# SwitchEthernet_-_Rev_A5.net
KiCad netlist of a schematic drawn in EAGLE
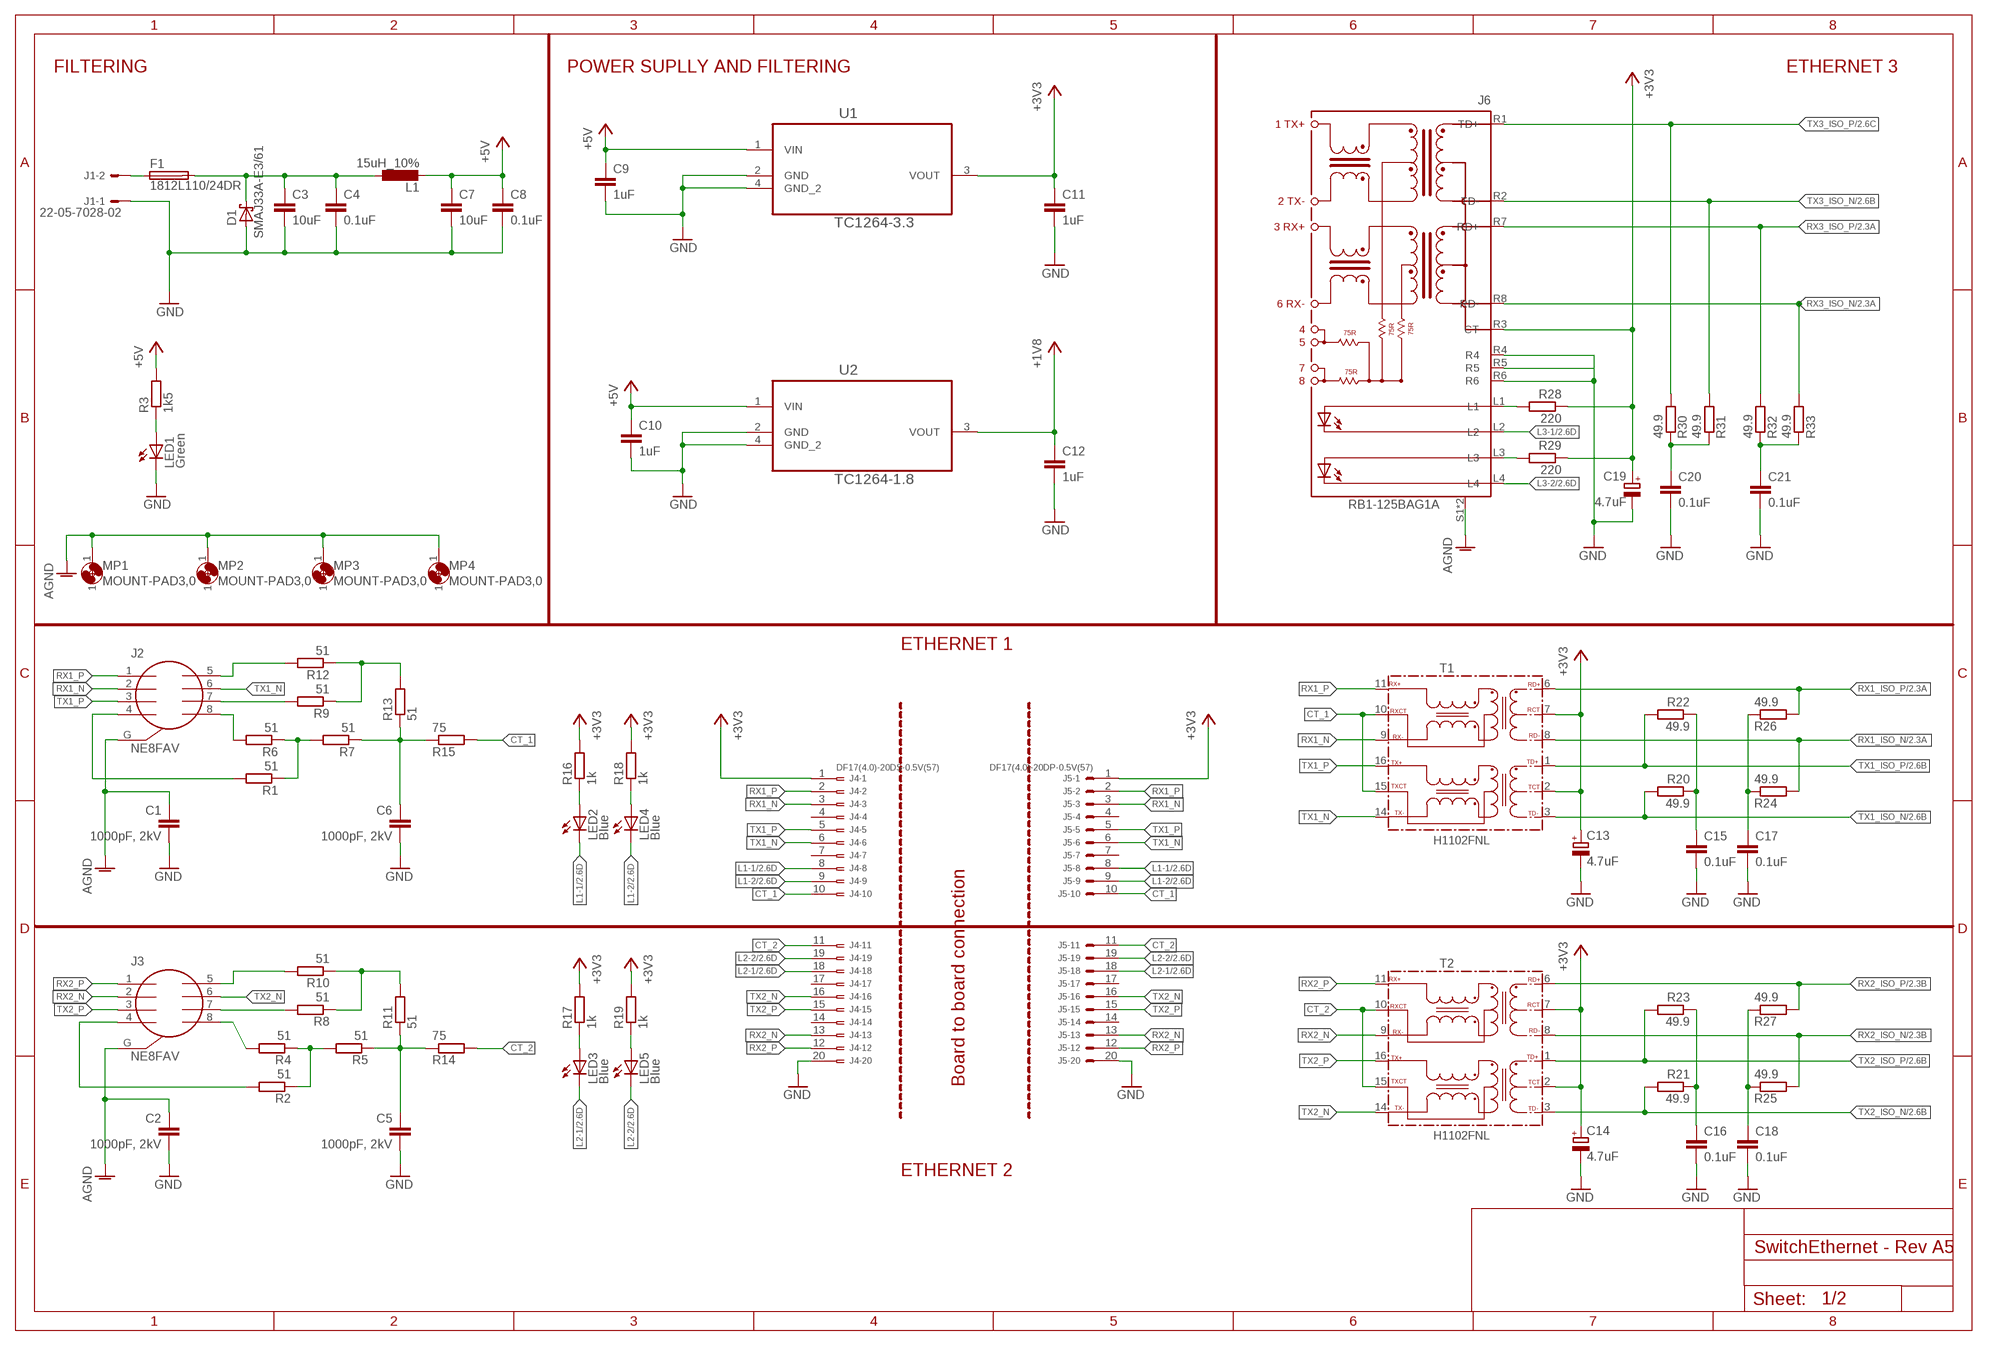
[diagram p0: schematic, sheet 1]
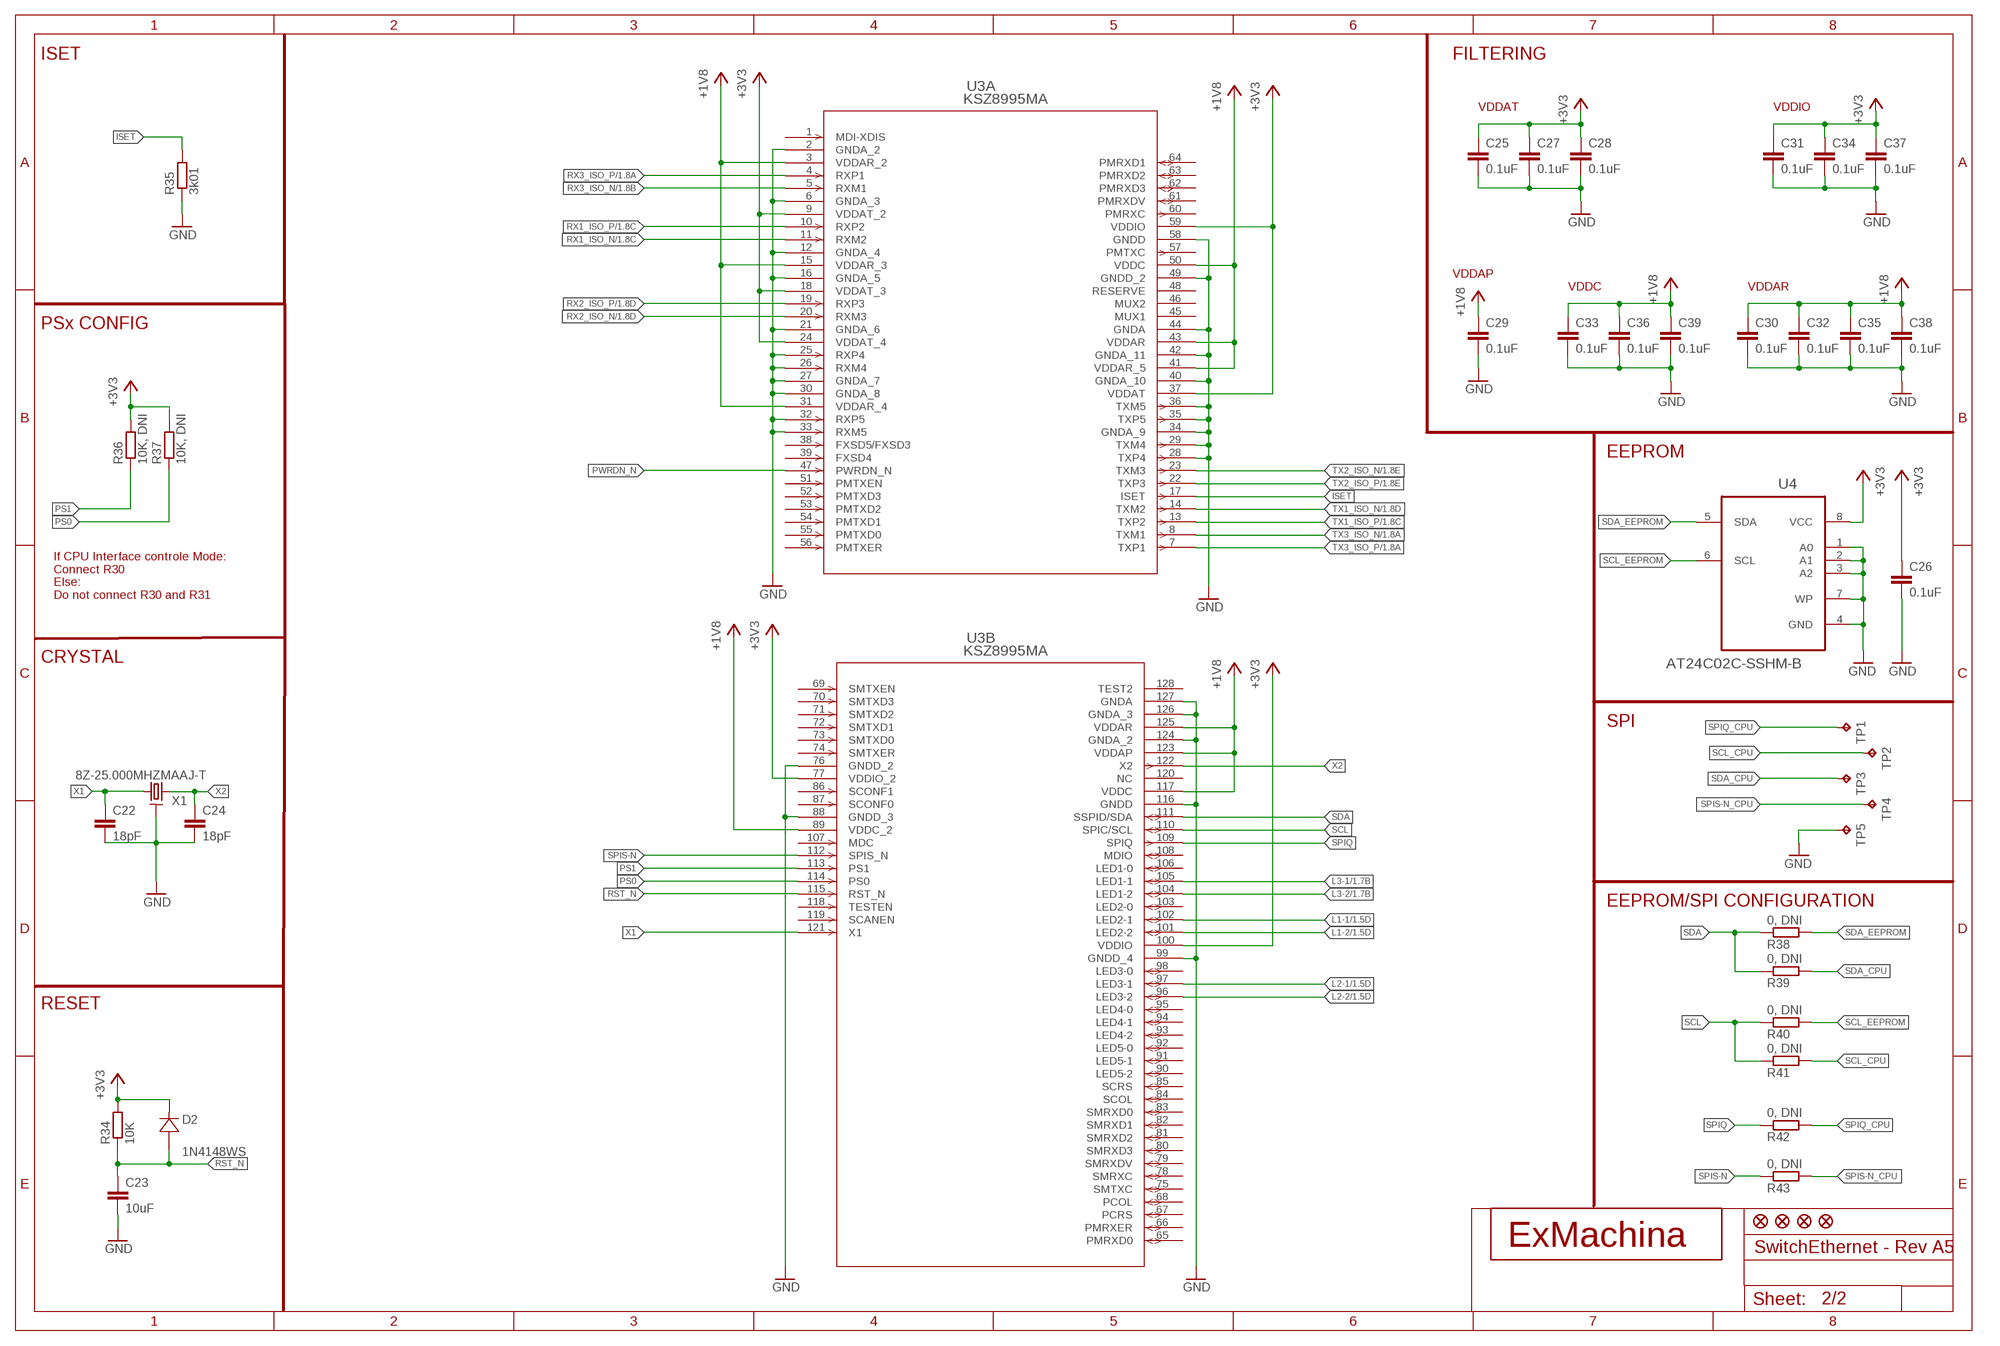
[diagram p1: schematic, sheet 2]

(export (version "E")
  (design (tool "Eeschema 10.0.6"))
  (components
    (comp (ref "C22")
      (value "18pF")
      (footprint "eagle-import:C0603")
      (fields (field (name "MPN") "MC0603N180J500CT"))
      (libsource (lib "eagle-import") (part "C-EUC0603"))
    )
    (comp (ref "C23")
      (value "10uF")
      (footprint "eagle-import:C0603")
      (fields (field (name "MPN") "GRM188R60J106ME47D"))
      (libsource (lib "eagle-import") (part "C-EUC0603"))
    )
    (comp (ref "C24")
      (value "18pF")
      (footprint "eagle-import:C0603")
      (fields (field (name "MPN") "MC0603N180J500CT"))
      (libsource (lib "eagle-import") (part "C-EUC0603"))
    )
    (comp (ref "C25")
      (value "0.1uF")
      (footprint "eagle-import:C0603")
      (fields (field (name "MPN") "MC0603B104K160CT"))
      (libsource (lib "eagle-import") (part "C-EUC0603"))
    )
    (comp (ref "C26")
      (value "0.1uF")
      (footprint "eagle-import:C0603")
      (fields (field (name "MPN") "MC0603B104K160CT"))
      (libsource (lib "eagle-import") (part "C-EUC0603"))
    )
    (comp (ref "C27")
      (value "0.1uF")
      (footprint "eagle-import:C0603")
      (fields (field (name "MPN") "MC0603B104K160CT"))
      (libsource (lib "eagle-import") (part "C-EUC0603"))
    )
    (comp (ref "C28")
      (value "0.1uF")
      (footprint "eagle-import:C0603")
      (fields (field (name "MPN") "MC0603B104K160CT"))
      (libsource (lib "eagle-import") (part "C-EUC0603"))
    )
    (comp (ref "C29")
      (value "0.1uF")
      (footprint "eagle-import:C0603")
      (fields (field (name "MPN") "MC0603B104K160CT"))
      (libsource (lib "eagle-import") (part "C-EUC0603"))
    )
    (comp (ref "C30")
      (value "0.1uF")
      (footprint "eagle-import:C0603")
      (fields (field (name "MPN") "MC0603B104K160CT"))
      (libsource (lib "eagle-import") (part "C-EUC0603"))
    )
    (comp (ref "C31")
      (value "0.1uF")
      (footprint "eagle-import:C0603")
      (fields (field (name "MPN") "MC0603B104K160CT"))
      (libsource (lib "eagle-import") (part "C-EUC0603"))
    )
    (comp (ref "C32")
      (value "0.1uF")
      (footprint "eagle-import:C0603")
      (fields (field (name "MPN") "MC0603B104K160CT"))
      (libsource (lib "eagle-import") (part "C-EUC0603"))
    )
    (comp (ref "C33")
      (value "0.1uF")
      (footprint "eagle-import:C0603")
      (fields (field (name "MPN") "MC0603B104K160CT"))
      (libsource (lib "eagle-import") (part "C-EUC0603"))
    )
    (comp (ref "C34")
      (value "0.1uF")
      (footprint "eagle-import:C0603")
      (fields (field (name "MPN") "MC0603B104K160CT"))
      (libsource (lib "eagle-import") (part "C-EUC0603"))
    )
    (comp (ref "C35")
      (value "0.1uF")
      (footprint "eagle-import:C0603")
      (fields (field (name "MPN") "MC0603B104K160CT"))
      (libsource (lib "eagle-import") (part "C-EUC0603"))
    )
    (comp (ref "C36")
      (value "0.1uF")
      (footprint "eagle-import:C0603")
      (fields (field (name "MPN") "MC0603B104K160CT"))
      (libsource (lib "eagle-import") (part "C-EUC0603"))
    )
    (comp (ref "C37")
      (value "0.1uF")
      (footprint "eagle-import:C0603")
      (fields (field (name "MPN") "MC0603B104K160CT"))
      (libsource (lib "eagle-import") (part "C-EUC0603"))
    )
    (comp (ref "C38")
      (value "0.1uF")
      (footprint "eagle-import:C0603")
      (fields (field (name "MPN") "MC0603B104K160CT"))
      (libsource (lib "eagle-import") (part "C-EUC0603"))
    )
    (comp (ref "C39")
      (value "0.1uF")
      (footprint "eagle-import:C0603")
      (fields (field (name "MPN") "MC0603B104K160CT"))
      (libsource (lib "eagle-import") (part "C-EUC0603"))
    )
    (comp (ref "D2")
      (value "1N4148WS")
      (footprint "eagle-import:SOD323-W")
      (fields (field (name "MPN") "1N4148WS."))
      (libsource (lib "eagle-import") (part "1N4148WS"))
    )
    (comp (ref "JP1")
      (value "FIDUCIAL1X2")
      (footprint "eagle-import:FIDUCIAL-1X2")
      (libsource (lib "eagle-import") (part "FIDUCIAL1X2"))
    )
    (comp (ref "JP2")
      (value "FIDUCIAL1X2")
      (footprint "eagle-import:FIDUCIAL-1X2")
      (libsource (lib "eagle-import") (part "FIDUCIAL1X2"))
    )
    (comp (ref "JP3")
      (value "FIDUCIAL1X2")
      (footprint "eagle-import:FIDUCIAL-1X2")
      (libsource (lib "eagle-import") (part "FIDUCIAL1X2"))
    )
    (comp (ref "JP4")
      (value "FIDUCIAL1X2")
      (footprint "eagle-import:FIDUCIAL-1X2")
      (libsource (lib "eagle-import") (part "FIDUCIAL1X2"))
    )
    (comp (ref "R34")
      (value "10K")
      (footprint "eagle-import:R0603")
      (fields (field (name "MF") "Multicomp Passives") (field (name "MPN") "MC0063W0603110K"))
      (libsource (lib "eagle-import") (part "R-EU_R0603"))
    )
    (comp (ref "R35")
      (value "3k01")
      (footprint "eagle-import:R0603")
      (fields (field (name "MPN") "MC0063W060313K01"))
      (libsource (lib "eagle-import") (part "R-EU_R0603"))
    )
    (comp (ref "R36")
      (value "10K, DNI")
      (footprint "eagle-import:R0603")
      (fields (field (name "MF") "Multicomp Passives") (field (name "MPN") "MC0063W0603110K"))
      (libsource (lib "eagle-import") (part "R-EU_R0603"))
    )
    (comp (ref "R37")
      (value "10K, DNI")
      (footprint "eagle-import:R0603")
      (fields (field (name "MF") "Multicomp Passives") (field (name "MPN") "MC0063W0603110K"))
      (libsource (lib "eagle-import") (part "R-EU_R0603"))
    )
    (comp (ref "R38")
      (value "0, DNI")
      (footprint "eagle-import:R0603")
      (fields (field (name "MF") "Multicomp Passives") (field (name "MPN") "MC0603WG00000T5E-TC"))
      (libsource (lib "eagle-import") (part "R-EU_R0603"))
    )
    (comp (ref "R39")
      (value "0, DNI")
      (footprint "eagle-import:R0603")
      (fields (field (name "MF") "Multicomp Passives") (field (name "MPN") "MC0603WG00000T5E-TC"))
      (libsource (lib "eagle-import") (part "R-EU_R0603"))
    )
    (comp (ref "R40")
      (value "0, DNI")
      (footprint "eagle-import:R0603")
      (fields (field (name "MF") "Multicomp Passives") (field (name "MPN") "MC0603WG00000T5E-TC"))
      (libsource (lib "eagle-import") (part "R-EU_R0603"))
    )
    (comp (ref "R41")
      (value "0, DNI")
      (footprint "eagle-import:R0603")
      (fields (field (name "MF") "Multicomp Passives") (field (name "MPN") "MC0603WG00000T5E-TC"))
      (libsource (lib "eagle-import") (part "R-EU_R0603"))
    )
    (comp (ref "R42")
      (value "0, DNI")
      (footprint "eagle-import:R0603")
      (fields (field (name "MF") "Multicomp Passives") (field (name "MPN") "MC0603WG00000T5E-TC"))
      (libsource (lib "eagle-import") (part "R-EU_R0603"))
    )
    (comp (ref "R43")
      (value "0, DNI")
      (footprint "eagle-import:R0603")
      (fields (field (name "MF") "Multicomp Passives") (field (name "MPN") "MC0603WG00000T5E-TC"))
      (libsource (lib "eagle-import") (part "R-EU_R0603"))
    )
    (comp (ref "T3")
      (value "EXMACHINA-LOGO-NAME")
      (footprint "eagle-import:EXM-LOGO-BASELINE")
      (libsource (lib "eagle-import") (part "EXMACHINA-LOGO-NAME"))
    )
    (comp (ref "TP1")
      (value "TPB1,27")
      (footprint "eagle-import:B1,27")
      (libsource (lib "eagle-import") (part "TPB1,27"))
    )
    (comp (ref "TP2")
      (value "TPB1,27")
      (footprint "eagle-import:B1,27")
      (libsource (lib "eagle-import") (part "TPB1,27"))
    )
    (comp (ref "TP3")
      (value "TPB1,27")
      (footprint "eagle-import:B1,27")
      (libsource (lib "eagle-import") (part "TPB1,27"))
    )
    (comp (ref "TP4")
      (value "TPB1,27")
      (footprint "eagle-import:B1,27")
      (libsource (lib "eagle-import") (part "TPB1,27"))
    )
    (comp (ref "TP5")
      (value "TPB1,27")
      (footprint "eagle-import:B1,27")
      (libsource (lib "eagle-import") (part "TPB1,27"))
    )
    (comp (ref "U3")
      (value "KSZ8995MA")
      (footprint "eagle-import:PQFP-128_MQL")
      (fields
        (field (name "MANUFACTURER_PART_NUMBER") "ksz8995ma")
        (field (name "OC_FARNELL") "2509844")
        (field (name "OC_NEWARK") "unknown")
        (field (name "COPYRIGHT") "Copyright (C) 2015 Accelerated Designs. All rights reserved")
      )
      (libsource (lib "eagle-import") (part "KSZ8995MA"))
    )
    (comp (ref "U4")
      (value "AT24C02C-SSHM-B")
      (footprint "eagle-import:SOIC127P600X175-8N")
      (fields (field (name "OC_FARNELL") "1971995"))
      (libsource (lib "eagle-import") (part "AT24C02C-SSHM-B"))
    )
    (comp (ref "X1")
      (value "8Z-25.000MHZMAAJ-T")
      (footprint "eagle-import:SMD2.5X2")
      (fields (field (name "MPN") "8Z-25.000MAAJ-T"))
      (libsource (lib "eagle-import") (part "8Z-25.000MHZMAAJ-T"))
    )
    (comp (ref "C1")
      (value "1000pF, 2kV")
      (footprint "eagle-import:C1206")
      (fields (field (name "MPN") "MC1206B102K202CT"))
      (libsource (lib "eagle-import") (part "C-EUC1206"))
    )
    (comp (ref "C2")
      (value "1000pF, 2kV")
      (footprint "eagle-import:C1206")
      (fields (field (name "MPN") "MC1206B102K202CT"))
      (libsource (lib "eagle-import") (part "C-EUC1206"))
    )
    (comp (ref "C3")
      (value "10uF")
      (footprint "eagle-import:C0603")
      (fields (field (name "MPN") "GRM188R60J106ME47D"))
      (libsource (lib "eagle-import") (part "C-EUC0603"))
    )
    (comp (ref "C4")
      (value "0.1uF")
      (footprint "eagle-import:C0603")
      (fields (field (name "MPN") "MC0603B104K160CT"))
      (libsource (lib "eagle-import") (part "C-EUC0603"))
    )
    (comp (ref "C5")
      (value "1000pF, 2kV")
      (footprint "eagle-import:C1206")
      (fields (field (name "MPN") "MC1206B102K202CT"))
      (libsource (lib "eagle-import") (part "C-EUC1206"))
    )
    (comp (ref "C6")
      (value "1000pF, 2kV")
      (footprint "eagle-import:C1206")
      (fields (field (name "MPN") "MC1206B102K202CT"))
      (libsource (lib "eagle-import") (part "C-EUC1206"))
    )
    (comp (ref "C7")
      (value "10uF")
      (footprint "eagle-import:C0603")
      (fields (field (name "MPN") "GRM188R60J106ME47D"))
      (libsource (lib "eagle-import") (part "C-EUC0603"))
    )
    (comp (ref "C8")
      (value "0.1uF")
      (footprint "eagle-import:C0603")
      (fields (field (name "MPN") "MC0603B104K160CT"))
      (libsource (lib "eagle-import") (part "C-EUC0603"))
    )
    (comp (ref "C9")
      (value "1uF")
      (footprint "eagle-import:C0603")
      (fields (field (name "MPN") "MC0603B105K160CT"))
      (libsource (lib "eagle-import") (part "C-EUC0603"))
    )
    (comp (ref "C10")
      (value "1uF")
      (footprint "eagle-import:C0603")
      (fields (field (name "MPN") "MC0603B105K160CT"))
      (libsource (lib "eagle-import") (part "C-EUC0603"))
    )
    (comp (ref "C11")
      (value "1uF")
      (footprint "eagle-import:C0603")
      (fields (field (name "MPN") "MC0603B105K160CT"))
      (libsource (lib "eagle-import") (part "C-EUC0603"))
    )
    (comp (ref "C12")
      (value "1uF")
      (footprint "eagle-import:C0603")
      (fields (field (name "MPN") "MC0603B105K160CT"))
      (libsource (lib "eagle-import") (part "C-EUC0603"))
    )
    (comp (ref "C13")
      (value "4.7uF")
      (footprint "eagle-import:CT3216")
      (fields (field (name "MPN") "MCCTA475M010"))
      (libsource (lib "eagle-import") (part "CPOL-EUCT3216"))
    )
    (comp (ref "C14")
      (value "4.7uF")
      (footprint "eagle-import:CT3216")
      (fields (field (name "MPN") "MCCTA475M010"))
      (libsource (lib "eagle-import") (part "CPOL-EUCT3216"))
    )
    (comp (ref "C15")
      (value "0.1uF")
      (footprint "eagle-import:C0603")
      (fields (field (name "MPN") "MC0603B104K160CT"))
      (libsource (lib "eagle-import") (part "C-EUC0603"))
    )
    (comp (ref "C16")
      (value "0.1uF")
      (footprint "eagle-import:C0603")
      (fields (field (name "MPN") "MC0603B104K160CT"))
      (libsource (lib "eagle-import") (part "C-EUC0603"))
    )
    (comp (ref "C17")
      (value "0.1uF")
      (footprint "eagle-import:C0603")
      (fields (field (name "MPN") "MC0603B104K160CT"))
      (libsource (lib "eagle-import") (part "C-EUC0603"))
    )
    (comp (ref "C18")
      (value "0.1uF")
      (footprint "eagle-import:C0603")
      (fields (field (name "MPN") "MC0603B104K160CT"))
      (libsource (lib "eagle-import") (part "C-EUC0603"))
    )
    (comp (ref "C19")
      (value "4.7uF")
      (footprint "eagle-import:CT3216")
      (fields (field (name "MPN") "MCCTA475M010"))
      (libsource (lib "eagle-import") (part "CPOL-EUCT3216"))
    )
    (comp (ref "C20")
      (value "0.1uF")
      (footprint "eagle-import:C0603")
      (fields (field (name "MPN") "MC0603B104K160CT"))
      (libsource (lib "eagle-import") (part "C-EUC0603"))
    )
    (comp (ref "C21")
      (value "0.1uF")
      (footprint "eagle-import:C0603")
      (fields (field (name "MPN") "MC0603B104K160CT"))
      (libsource (lib "eagle-import") (part "C-EUC0603"))
    )
    (comp (ref "D1")
      (value "SMAJ33A-E3/61")
      (footprint "eagle-import:DIODE_DO-214AC")
      (fields
        (field (name "RSPARTNUMBER") "7103462")
        (field (name "COPYRIGHT") "Copyright (C) 2015 Accelerated Designs. All rights reserved")
      )
      (libsource (lib "eagle-import") (part "SMAJ33A-E3/61"))
    )
    (comp (ref "F1")
      (value "1812L110/24DR")
      (footprint "eagle-import:LITTLEFUSE_SMD")
      (libsource (lib "eagle-import") (part "1812L110/24DR"))
    )
    (comp (ref "J1")
      (value "22-05-7028-02")
      (footprint "eagle-import:7395-02")
      (fields (field (name "MPN") "22-05-7028") (field (name "OC_NEWARK") "25M1728"))
      (libsource (lib "eagle-import") (part "22-?-0205-7028"))
    )
    (comp (ref "J2")
      (value "NE8FAV")
      (footprint "eagle-import:NE8FAV")
      (fields (field (name "MF") "NEUTRIK") (field (name "OC_FARNELL") "1202031"))
      (libsource (lib "eagle-import") (part "NE8FAV"))
    )
    (comp (ref "J3")
      (value "NE8FAV")
      (footprint "eagle-import:NE8FAV")
      (fields (field (name "MF") "NEUTRIK") (field (name "OC_FARNELL") "1202031"))
      (libsource (lib "eagle-import") (part "NE8FAV"))
    )
    (comp (ref "J4")
      (value "DF17(4.0)-20DS-0.5V(57)")
      (footprint "eagle-import:DF17-20DS")
      (fields (field (name "MPN") "DF17(4.0)-20DS-0.5V(57)") (field (name "OC_NEWARK") "69W0567"))
      (libsource (lib "eagle-import") (part "DF17(?)-20DS-0.5V(57)4.0"))
    )
    (comp (ref "J5")
      (value "DF17(4.0)-20DP-0.5V(57)")
      (footprint "eagle-import:DF17-20DP")
      (fields (field (name "MPN") "DF17(4.0)-20DP-0.5V(57)") (field (name "OC_NEWARK") "69W0566"))
      (libsource (lib "eagle-import") (part "DF17(?)-20DP-0.5V(57)4.0"))
    )
    (comp (ref "J6")
      (value "RB1-125BAG1A")
      (footprint "eagle-import:WIZNET_RB1-125BAG1A")
      (libsource (lib "eagle-import") (part "RB1-125BAG1A"))
    )
    (comp (ref "L1")
      (value "15uH_10%")
      (footprint "eagle-import:L4532M")
      (fields (field (name "MPN") "LQH43CN150K03L"))
      (libsource (lib "eagle-import") (part "L-EUL4532C"))
    )
    (comp (ref "LED1")
      (value "Green")
      (footprint "eagle-import:CHIP-LED0603")
      (fields (field (name "MPN") "OVS-0604"))
      (libsource (lib "eagle-import") (part "LEDCHIP-LED0603"))
    )
    (comp (ref "LED2")
      (value "Blue")
      (footprint "eagle-import:CHIP-LED0603")
      (fields (field (name "MPN") "OVS-0603"))
      (libsource (lib "eagle-import") (part "LEDCHIP-LED0603"))
    )
    (comp (ref "LED3")
      (value "Blue")
      (footprint "eagle-import:CHIP-LED0603")
      (fields (field (name "MPN") "OVS-0603"))
      (libsource (lib "eagle-import") (part "LEDCHIP-LED0603"))
    )
    (comp (ref "LED4")
      (value "Blue")
      (footprint "eagle-import:CHIP-LED0603")
      (fields (field (name "MPN") "OVS-0603"))
      (libsource (lib "eagle-import") (part "LEDCHIP-LED0603"))
    )
    (comp (ref "LED5")
      (value "Blue")
      (footprint "eagle-import:CHIP-LED0603")
      (fields (field (name "MPN") "OVS-0603"))
      (libsource (lib "eagle-import") (part "LEDCHIP-LED0603"))
    )
    (comp (ref "MP1")
      (value "MOUNT-PAD3,0")
      (footprint "eagle-import:P3,0")
      (libsource (lib "eagle-import") (part "MOUNT-PAD3,0"))
    )
    (comp (ref "MP2")
      (value "MOUNT-PAD3,0")
      (footprint "eagle-import:P3,0")
      (libsource (lib "eagle-import") (part "MOUNT-PAD3,0"))
    )
    (comp (ref "MP3")
      (value "MOUNT-PAD3,0")
      (footprint "eagle-import:P3,0")
      (libsource (lib "eagle-import") (part "MOUNT-PAD3,0"))
    )
    (comp (ref "MP4")
      (value "MOUNT-PAD3,0")
      (footprint "eagle-import:P3,0")
      (libsource (lib "eagle-import") (part "MOUNT-PAD3,0"))
    )
    (comp (ref "R1")
      (value "51")
      (footprint "eagle-import:R0603")
      (fields (field (name "MF") "Multicomp Passives") (field (name "MPN") "MC0063W0603151R"))
      (libsource (lib "eagle-import") (part "R-EU_R0603"))
    )
    (comp (ref "R2")
      (value "51")
      (footprint "eagle-import:R0603")
      (fields (field (name "MF") "Multicomp Passives") (field (name "MPN") "MC0063W0603151R"))
      (libsource (lib "eagle-import") (part "R-EU_R0603"))
    )
    (comp (ref "R3")
      (value "1k5")
      (footprint "eagle-import:R0603")
      (fields (field (name "MF") "Multicomp Passives") (field (name "MPN") "MC0063W060311K5"))
      (libsource (lib "eagle-import") (part "R-EU_R0603"))
    )
    (comp (ref "R4")
      (value "51")
      (footprint "eagle-import:R0603")
      (fields (field (name "MF") "Multicomp Passives") (field (name "MPN") "MC0063W0603151R"))
      (libsource (lib "eagle-import") (part "R-EU_R0603"))
    )
    (comp (ref "R5")
      (value "51")
      (footprint "eagle-import:R0603")
      (fields (field (name "MF") "Multicomp Passives") (field (name "MPN") "MC0063W0603151R"))
      (libsource (lib "eagle-import") (part "R-EU_R0603"))
    )
    (comp (ref "R6")
      (value "51")
      (footprint "eagle-import:R0603")
      (fields (field (name "MF") "Multicomp Passives") (field (name "MPN") "MC0063W0603151R"))
      (libsource (lib "eagle-import") (part "R-EU_R0603"))
    )
    (comp (ref "R7")
      (value "51")
      (footprint "eagle-import:R0603")
      (fields (field (name "MF") "Multicomp Passives") (field (name "MPN") "MC0063W0603151R"))
      (libsource (lib "eagle-import") (part "R-EU_R0603"))
    )
    (comp (ref "R8")
      (value "51")
      (footprint "eagle-import:R0603")
      (fields (field (name "MF") "Multicomp Passives") (field (name "MPN") "MC0063W0603151R"))
      (libsource (lib "eagle-import") (part "R-EU_R0603"))
    )
    (comp (ref "R9")
      (value "51")
      (footprint "eagle-import:R0603")
      (fields (field (name "MF") "Multicomp Passives") (field (name "MPN") "MC0063W0603151R"))
      (libsource (lib "eagle-import") (part "R-EU_R0603"))
    )
    (comp (ref "R10")
      (value "51")
      (footprint "eagle-import:R0603")
      (fields (field (name "MF") "Multicomp Passives") (field (name "MPN") "MC0063W0603151R"))
      (libsource (lib "eagle-import") (part "R-EU_R0603"))
    )
    (comp (ref "R11")
      (value "51")
      (footprint "eagle-import:R0603")
      (fields (field (name "MF") "Multicomp Passives") (field (name "MPN") "MC0063W0603151R"))
      (libsource (lib "eagle-import") (part "R-EU_R0603"))
    )
    (comp (ref "R12")
      (value "51")
      (footprint "eagle-import:R0603")
      (fields (field (name "MF") "Multicomp Passives") (field (name "MPN") "MC0063W0603151R"))
      (libsource (lib "eagle-import") (part "R-EU_R0603"))
    )
    (comp (ref "R13")
      (value "51")
      (footprint "eagle-import:R0603")
      (fields (field (name "MF") "Multicomp Passives") (field (name "MPN") "MC0063W0603151R"))
      (libsource (lib "eagle-import") (part "R-EU_R0603"))
    )
    (comp (ref "R14")
      (value "75")
      (footprint "eagle-import:R0603")
      (fields (field (name "MF") "Multicomp Passives") (field (name "MPN") "MC0063W0603175R"))
      (libsource (lib "eagle-import") (part "R-EU_R0603"))
    )
    (comp (ref "R15")
      (value "75")
      (footprint "eagle-import:R0603")
      (fields (field (name "MF") "Multicomp Passives") (field (name "MPN") "MC0063W0603175R"))
      (libsource (lib "eagle-import") (part "R-EU_R0603"))
    )
    (comp (ref "R16")
      (value "1k")
      (footprint "eagle-import:R0603")
      (fields (field (name "MPN") "MCMR06X1001FTL"))
      (libsource (lib "eagle-import") (part "R-EU_R0603"))
    )
    (comp (ref "R17")
      (value "1k")
      (footprint "eagle-import:R0603")
      (fields (field (name "MPN") "MCMR06X1001FTL"))
      (libsource (lib "eagle-import") (part "R-EU_R0603"))
    )
    (comp (ref "R18")
      (value "1k")
      (footprint "eagle-import:R0603")
      (fields (field (name "MPN") "MCMR06X1001FTL"))
      (libsource (lib "eagle-import") (part "R-EU_R0603"))
    )
    (comp (ref "R19")
      (value "1k")
      (footprint "eagle-import:R0603")
      (fields (field (name "MPN") "MCMR06X1001FTL"))
      (libsource (lib "eagle-import") (part "R-EU_R0603"))
    )
    (comp (ref "R20")
      (value "49.9")
      (footprint "eagle-import:R0603")
      (fields (field (name "MPN") "MC0603SAF499JT5E"))
      (libsource (lib "eagle-import") (part "R-EU_R0603"))
    )
    (comp (ref "R21")
      (value "49.9")
      (footprint "eagle-import:R0603")
      (fields (field (name "MPN") "MC0603SAF499JT5E"))
      (libsource (lib "eagle-import") (part "R-EU_R0603"))
    )
    (comp (ref "R22")
      (value "49.9")
      (footprint "eagle-import:R0603")
      (fields (field (name "MPN") "MC0603SAF499JT5E"))
      (libsource (lib "eagle-import") (part "R-EU_R0603"))
    )
    (comp (ref "R23")
      (value "49.9")
      (footprint "eagle-import:R0603")
      (fields (field (name "MPN") "MC0603SAF499JT5E"))
      (libsource (lib "eagle-import") (part "R-EU_R0603"))
    )
    (comp (ref "R24")
      (value "49.9")
      (footprint "eagle-import:R0603")
      (fields (field (name "MPN") "MC0603SAF499JT5E"))
      (libsource (lib "eagle-import") (part "R-EU_R0603"))
    )
    (comp (ref "R25")
      (value "49.9")
      (footprint "eagle-import:R0603")
      (fields (field (name "MPN") "MC0603SAF499JT5E"))
      (libsource (lib "eagle-import") (part "R-EU_R0603"))
    )
    (comp (ref "R26")
      (value "49.9")
      (footprint "eagle-import:R0603")
      (fields (field (name "MPN") "MC0603SAF499JT5E"))
      (libsource (lib "eagle-import") (part "R-EU_R0603"))
    )
    (comp (ref "R27")
      (value "49.9")
      (footprint "eagle-import:R0603")
      (fields (field (name "MPN") "MC0603SAF499JT5E"))
      (libsource (lib "eagle-import") (part "R-EU_R0603"))
    )
    (comp (ref "R28")
      (value "220")
      (footprint "eagle-import:R0603")
      (fields (field (name "MF") "Multicomp Passives") (field (name "MPN") "MC0063W06031220R"))
      (libsource (lib "eagle-import") (part "R-EU_R0603"))
    )
    (comp (ref "R29")
      (value "220")
      (footprint "eagle-import:R0603")
      (fields (field (name "MF") "Multicomp Passives") (field (name "MPN") "MC0063W06031220R"))
      (libsource (lib "eagle-import") (part "R-EU_R0603"))
    )
    (comp (ref "R30")
      (value "49.9")
      (footprint "eagle-import:R0603")
      (fields (field (name "MPN") "MC0603SAF499JT5E"))
      (libsource (lib "eagle-import") (part "R-EU_R0603"))
    )
    (comp (ref "R31")
      (value "49.9")
      (footprint "eagle-import:R0603")
      (fields (field (name "MPN") "MC0603SAF499JT5E"))
      (libsource (lib "eagle-import") (part "R-EU_R0603"))
    )
    (comp (ref "R32")
      (value "49.9")
      (footprint "eagle-import:R0603")
      (fields (field (name "MPN") "MC0603SAF499JT5E"))
      (libsource (lib "eagle-import") (part "R-EU_R0603"))
    )
    (comp (ref "R33")
      (value "49.9")
      (footprint "eagle-import:R0603")
      (fields (field (name "MPN") "MC0603SAF499JT5E"))
      (libsource (lib "eagle-import") (part "R-EU_R0603"))
    )
    (comp (ref "T1")
      (value "H1102FNL")
      (footprint "eagle-import:HXXXX")
      (libsource (lib "eagle-import") (part "H1102FNL"))
    )
    (comp (ref "T2")
      (value "H1102FNL")
      (footprint "eagle-import:HXXXX")
      (libsource (lib "eagle-import") (part "H1102FNL"))
    )
    (comp (ref "U1")
      (value "TC1264-3.3")
      (footprint "eagle-import:SOT230P700X180-4N")
      (fields (field (name "MF") "MICROCHIP") (field (name "MPN") "TC1264-3.3VDB"))
      (libsource (lib "eagle-import") (part "TC1264-3.3"))
    )
    (comp (ref "U2")
      (value "TC1264-1.8")
      (footprint "eagle-import:SOT230P700X180-4N")
      (fields (field (name "MF") "MICROCHIP") (field (name "MPN") "TC1264-1.8VDBTR"))
      (libsource (lib "eagle-import") (part "TC1264-1.8"))
    )
  )
  (nets
    (net (code "1") (name "+1V8") (class "Default")
      (node (ref "C12") (pin "1") (pinfunction "1_1") (pintype "passive"))
      (node (ref "C29") (pin "1") (pinfunction "1_1") (pintype "passive"))
      (node (ref "C30") (pin "1") (pinfunction "1_1") (pintype "passive"))
      (node (ref "C32") (pin "1") (pinfunction "1_1") (pintype "passive"))
      (node (ref "C33") (pin "1") (pinfunction "1_1") (pintype "passive"))
      (node (ref "C35") (pin "1") (pinfunction "1_1") (pintype "passive"))
      (node (ref "C36") (pin "1") (pinfunction "1_1") (pintype "passive"))
      (node (ref "C38") (pin "1") (pinfunction "1_1") (pintype "passive"))
      (node (ref "C39") (pin "1") (pinfunction "1_1") (pintype "passive"))
      (node (ref "U2") (pin "3") (pinfunction "VOUT_3") (pintype "output"))
      (node (ref "U3") (pin "117") (pinfunction "VDDC_117") (pintype "power_in"))
      (node (ref "U3") (pin "123") (pinfunction "VDDAP_123") (pintype "power_in"))
      (node (ref "U3") (pin "125") (pinfunction "VDDAR_125") (pintype "power_in"))
      (node (ref "U3") (pin "15") (pinfunction "VDDAR_3_15") (pintype "power_in"))
      (node (ref "U3") (pin "3") (pinfunction "VDDAR_2_3") (pintype "power_in"))
      (node (ref "U3") (pin "31") (pinfunction "VDDAR_4_31") (pintype "power_in"))
      (node (ref "U3") (pin "41") (pinfunction "VDDAR_5_41") (pintype "power_in"))
      (node (ref "U3") (pin "43") (pinfunction "VDDAR_43") (pintype "power_in"))
      (node (ref "U3") (pin "50") (pinfunction "VDDC_50") (pintype "power_in"))
      (node (ref "U3") (pin "89") (pinfunction "VDDC_2_89") (pintype "power_in"))
    )
    (net (code "2") (name "+3V3") (class "Default")
      (node (ref "C11") (pin "1") (pinfunction "1_1") (pintype "passive"))
      (node (ref "C13") (pin "+") (pinfunction "+_+") (pintype "passive"))
      (node (ref "C14") (pin "+") (pinfunction "+_+") (pintype "passive"))
      (node (ref "C19") (pin "+") (pinfunction "+_+") (pintype "passive"))
      (node (ref "C25") (pin "1") (pinfunction "1_1") (pintype "passive"))
      (node (ref "C26") (pin "1") (pinfunction "1_1") (pintype "passive"))
      (node (ref "C27") (pin "1") (pinfunction "1_1") (pintype "passive"))
      (node (ref "C28") (pin "1") (pinfunction "1_1") (pintype "passive"))
      (node (ref "C31") (pin "1") (pinfunction "1_1") (pintype "passive"))
      (node (ref "C34") (pin "1") (pinfunction "1_1") (pintype "passive"))
      (node (ref "C37") (pin "1") (pinfunction "1_1") (pintype "passive"))
      (node (ref "D2") (pin "C") (pinfunction "1_C") (pintype "passive"))
      (node (ref "J4") (pin "1") (pinfunction "P_1") (pintype "bidirectional"))
      (node (ref "J5") (pin "1") (pinfunction "P_1") (pintype "bidirectional"))
      (node (ref "J6") (pin "R3") (pinfunction "CT_R3") (pintype "input"))
      (node (ref "R16") (pin "2") (pinfunction "2_2") (pintype "passive"))
      (node (ref "R17") (pin "2") (pinfunction "2_2") (pintype "passive"))
      (node (ref "R18") (pin "2") (pinfunction "2_2") (pintype "passive"))
      (node (ref "R19") (pin "2") (pinfunction "2_2") (pintype "passive"))
      (node (ref "R28") (pin "1") (pinfunction "1_1") (pintype "passive"))
      (node (ref "R29") (pin "1") (pinfunction "1_1") (pintype "passive"))
      (node (ref "R34") (pin "2") (pinfunction "2_2") (pintype "passive"))
      (node (ref "R36") (pin "2") (pinfunction "2_2") (pintype "passive"))
      (node (ref "R37") (pin "2") (pinfunction "2_2") (pintype "passive"))
      (node (ref "T1") (pin "2") (pinfunction "TCT_2") (pintype "bidirectional"))
      (node (ref "T1") (pin "7") (pinfunction "RCT_7") (pintype "bidirectional"))
      (node (ref "T2") (pin "2") (pinfunction "TCT_2") (pintype "bidirectional"))
      (node (ref "T2") (pin "7") (pinfunction "RCT_7") (pintype "bidirectional"))
      (node (ref "U1") (pin "3") (pinfunction "VOUT_3") (pintype "output"))
      (node (ref "U3") (pin "100") (pinfunction "VDDIO_100") (pintype "power_in"))
      (node (ref "U3") (pin "18") (pinfunction "VDDAT_3_18") (pintype "power_in"))
      (node (ref "U3") (pin "24") (pinfunction "VDDAT_4_24") (pintype "power_in"))
      (node (ref "U3") (pin "37") (pinfunction "VDDAT_37") (pintype "power_in"))
      (node (ref "U3") (pin "59") (pinfunction "VDDIO_59") (pintype "power_in"))
      (node (ref "U3") (pin "77") (pinfunction "VDDIO_2_77") (pintype "power_in"))
      (node (ref "U3") (pin "9") (pinfunction "VDDAT_2_9") (pintype "power_in"))
      (node (ref "U4") (pin "8") (pinfunction "VCC_8") (pintype "power_in"))
    )
    (net (code "3") (name "+5V") (class "Default")
      (node (ref "C10") (pin "1") (pinfunction "1_1") (pintype "passive"))
      (node (ref "C7") (pin "1") (pinfunction "1_1") (pintype "passive"))
      (node (ref "C8") (pin "1") (pinfunction "1_1") (pintype "passive"))
      (node (ref "C9") (pin "1") (pinfunction "1_1") (pintype "passive"))
      (node (ref "L1") (pin "2") (pinfunction "2_2") (pintype "passive"))
      (node (ref "R3") (pin "2") (pinfunction "2_2") (pintype "passive"))
      (node (ref "U1") (pin "1") (pinfunction "VIN_1") (pintype "input"))
      (node (ref "U2") (pin "1") (pinfunction "VIN_1") (pintype "input"))
    )
    (net (code "4") (name "AGND") (class "Default")
      (node (ref "C1") (pin "1") (pinfunction "1_1") (pintype "passive"))
      (node (ref "C2") (pin "1") (pinfunction "1_1") (pintype "passive"))
      (node (ref "J2") (pin "G") (pinfunction "G_G") (pintype "passive"))
      (node (ref "J3") (pin "G") (pinfunction "G_G") (pintype "passive"))
      (node (ref "J6") (pin "S1") (pinfunction "P$1_S1") (pintype "bidirectional"))
      (node (ref "J6") (pin "S2") (pinfunction "P$1_S2") (pintype "bidirectional"))
      (node (ref "MP1") (pin "1") (pinfunction "1_1") (pintype "power_in"))
      (node (ref "MP2") (pin "1") (pinfunction "1_1") (pintype "power_in"))
      (node (ref "MP3") (pin "1") (pinfunction "1_1") (pintype "power_in"))
      (node (ref "MP4") (pin "1") (pinfunction "1_1") (pintype "power_in"))
    )
    (net (code "5") (name "CT_1") (class "Default")
      (node (ref "J4") (pin "10") (pinfunction "P_10") (pintype "bidirectional"))
      (node (ref "J5") (pin "10") (pinfunction "P_10") (pintype "bidirectional"))
      (node (ref "R15") (pin "2") (pinfunction "2_2") (pintype "passive"))
      (node (ref "T1") (pin "10") (pinfunction "RXCT_10") (pintype "bidirectional"))
      (node (ref "T1") (pin "15") (pinfunction "TXCT_15") (pintype "bidirectional"))
    )
    (net (code "6") (name "CT_2") (class "Default")
      (node (ref "J4") (pin "11") (pinfunction "P_11") (pintype "bidirectional"))
      (node (ref "J5") (pin "11") (pinfunction "P_11") (pintype "bidirectional"))
      (node (ref "R14") (pin "2") (pinfunction "2_2") (pintype "passive"))
      (node (ref "T2") (pin "10") (pinfunction "RXCT_10") (pintype "bidirectional"))
      (node (ref "T2") (pin "15") (pinfunction "TXCT_15") (pintype "bidirectional"))
    )
    (net (code "7") (name "GND") (class "Default")
      (node (ref "C1") (pin "2") (pinfunction "2_2") (pintype "passive"))
      (node (ref "C10") (pin "2") (pinfunction "2_2") (pintype "passive"))
      (node (ref "C11") (pin "2") (pinfunction "2_2") (pintype "passive"))
      (node (ref "C12") (pin "2") (pinfunction "2_2") (pintype "passive"))
      (node (ref "C13") (pin "-") (pinfunction "-_-") (pintype "passive"))
      (node (ref "C14") (pin "-") (pinfunction "-_-") (pintype "passive"))
      (node (ref "C15") (pin "2") (pinfunction "2_2") (pintype "passive"))
      (node (ref "C16") (pin "2") (pinfunction "2_2") (pintype "passive"))
      (node (ref "C17") (pin "2") (pinfunction "2_2") (pintype "passive"))
      (node (ref "C18") (pin "2") (pinfunction "2_2") (pintype "passive"))
      (node (ref "C19") (pin "-") (pinfunction "-_-") (pintype "passive"))
      (node (ref "C2") (pin "2") (pinfunction "2_2") (pintype "passive"))
      (node (ref "C20") (pin "2") (pinfunction "2_2") (pintype "passive"))
      (node (ref "C21") (pin "2") (pinfunction "2_2") (pintype "passive"))
      (node (ref "C22") (pin "2") (pinfunction "2_2") (pintype "passive"))
      (node (ref "C23") (pin "2") (pinfunction "2_2") (pintype "passive"))
      (node (ref "C24") (pin "2") (pinfunction "2_2") (pintype "passive"))
      (node (ref "C25") (pin "2") (pinfunction "2_2") (pintype "passive"))
      (node (ref "C26") (pin "2") (pinfunction "2_2") (pintype "passive"))
      (node (ref "C27") (pin "2") (pinfunction "2_2") (pintype "passive"))
      (node (ref "C28") (pin "2") (pinfunction "2_2") (pintype "passive"))
      (node (ref "C29") (pin "2") (pinfunction "2_2") (pintype "passive"))
      (node (ref "C3") (pin "2") (pinfunction "2_2") (pintype "passive"))
      (node (ref "C30") (pin "2") (pinfunction "2_2") (pintype "passive"))
      (node (ref "C31") (pin "2") (pinfunction "2_2") (pintype "passive"))
      (node (ref "C32") (pin "2") (pinfunction "2_2") (pintype "passive"))
      (node (ref "C33") (pin "2") (pinfunction "2_2") (pintype "passive"))
      (node (ref "C34") (pin "2") (pinfunction "2_2") (pintype "passive"))
      (node (ref "C35") (pin "2") (pinfunction "2_2") (pintype "passive"))
      (node (ref "C36") (pin "2") (pinfunction "2_2") (pintype "passive"))
      (node (ref "C37") (pin "2") (pinfunction "2_2") (pintype "passive"))
      (node (ref "C38") (pin "2") (pinfunction "2_2") (pintype "passive"))
      (node (ref "C39") (pin "2") (pinfunction "2_2") (pintype "passive"))
      (node (ref "C4") (pin "2") (pinfunction "2_2") (pintype "passive"))
      (node (ref "C5") (pin "2") (pinfunction "2_2") (pintype "passive"))
      (node (ref "C6") (pin "2") (pinfunction "2_2") (pintype "passive"))
      (node (ref "C7") (pin "2") (pinfunction "2_2") (pintype "passive"))
      (node (ref "C8") (pin "2") (pinfunction "2_2") (pintype "passive"))
      (node (ref "C9") (pin "2") (pinfunction "2_2") (pintype "passive"))
      (node (ref "D1") (pin "2") (pinfunction "A_2") (pintype "passive"))
      (node (ref "J1") (pin "1") (pinfunction "S_1") (pintype "passive"))
      (node (ref "J4") (pin "20") (pinfunction "P_20") (pintype "bidirectional"))
      (node (ref "J5") (pin "20") (pinfunction "P_20") (pintype "bidirectional"))
      (node (ref "J6") (pin "R4") (pinfunction "R4_R4") (pintype "input"))
      (node (ref "J6") (pin "R5") (pinfunction "R5_R5") (pintype "input"))
      (node (ref "J6") (pin "R6") (pinfunction "R6_R6") (pintype "input"))
      (node (ref "LED1") (pin "C") (pinfunction "C_C") (pintype "passive"))
      (node (ref "R35") (pin "1") (pinfunction "1_1") (pintype "passive"))
      (node (ref "TP5") (pin "TP") (pinfunction "TP_TP") (pintype "input"))
      (node (ref "U1") (pin "2") (pinfunction "GND_2") (pintype "passive"))
      (node (ref "U1") (pin "4") (pinfunction "GND_2_4") (pintype "passive"))
      (node (ref "U2") (pin "2") (pinfunction "GND_2") (pintype "passive"))
      (node (ref "U2") (pin "4") (pinfunction "GND_2_4") (pintype "passive"))
      (node (ref "U3") (pin "116") (pinfunction "GNDD_116") (pintype "power_in"))
      (node (ref "U3") (pin "12") (pinfunction "GNDA_4_12") (pintype "power_in"))
      (node (ref "U3") (pin "124") (pinfunction "GNDA_2_124") (pintype "power_in"))
      (node (ref "U3") (pin "126") (pinfunction "GNDA_3_126") (pintype "power_in"))
      (node (ref "U3") (pin "127") (pinfunction "GNDA_127") (pintype "power_in"))
      (node (ref "U3") (pin "16") (pinfunction "GNDA_5_16") (pintype "power_in"))
      (node (ref "U3") (pin "2") (pinfunction "GNDA_2_2") (pintype "power_in"))
      (node (ref "U3") (pin "21") (pinfunction "GNDA_6_21") (pintype "power_in"))
      (node (ref "U3") (pin "25") (pinfunction "RXP4_25") (pintype "input"))
      (node (ref "U3") (pin "26") (pinfunction "RXM4_26") (pintype "input"))
      (node (ref "U3") (pin "27") (pinfunction "GNDA_7_27") (pintype "power_in"))
      (node (ref "U3") (pin "28") (pinfunction "TXP4_28") (pintype "output"))
      (node (ref "U3") (pin "29") (pinfunction "TXM4_29") (pintype "output"))
      (node (ref "U3") (pin "30") (pinfunction "GNDA_8_30") (pintype "power_in"))
      (node (ref "U3") (pin "32") (pinfunction "RXP5_32") (pintype "input"))
      (node (ref "U3") (pin "33") (pinfunction "RXM5_33") (pintype "input"))
      (node (ref "U3") (pin "34") (pinfunction "GNDA_9_34") (pintype "power_in"))
      (node (ref "U3") (pin "35") (pinfunction "TXP5_35") (pintype "output"))
      (node (ref "U3") (pin "36") (pinfunction "TXM5_36") (pintype "output"))
      (node (ref "U3") (pin "40") (pinfunction "GNDA_10_40") (pintype "power_in"))
      (node (ref "U3") (pin "42") (pinfunction "GNDA_11_42") (pintype "power_in"))
      (node (ref "U3") (pin "44") (pinfunction "GNDA_44") (pintype "power_in"))
      (node (ref "U3") (pin "49") (pinfunction "GNDD_2_49") (pintype "passive"))
      (node (ref "U3") (pin "58") (pinfunction "GNDD_58") (pintype "power_in"))
      (node (ref "U3") (pin "6") (pinfunction "GNDA_3_6") (pintype "power_in"))
      (node (ref "U3") (pin "76") (pinfunction "GNDD_2_76") (pintype "power_in"))
      (node (ref "U3") (pin "88") (pinfunction "GNDD_3_88") (pintype "power_in"))
      (node (ref "U3") (pin "99") (pinfunction "GNDD_4_99") (pintype "power_in"))
      (node (ref "U4") (pin "1") (pinfunction "A0_1") (pintype "input"))
      (node (ref "U4") (pin "2") (pinfunction "A1_2") (pintype "input"))
      (node (ref "U4") (pin "3") (pinfunction "A2_3") (pintype "input"))
      (node (ref "U4") (pin "4") (pinfunction "GND_4") (pintype "power_in"))
      (node (ref "U4") (pin "7") (pinfunction "WP_7") (pintype "input"))
      (node (ref "X1") (pin "2") (pinfunction "2_2") (pintype "passive"))
      (node (ref "X1") (pin "4") (pinfunction "2_4") (pintype "passive"))
    )
    (net (code "8") (name "ISET") (class "Default")
      (node (ref "R35") (pin "2") (pinfunction "2_2") (pintype "passive"))
      (node (ref "U3") (pin "17") (pinfunction "ISET_17") (pintype "output"))
    )
    (net (code "9") (name "L1-1") (class "Default")
      (node (ref "J4") (pin "8") (pinfunction "P_8") (pintype "bidirectional"))
      (node (ref "J5") (pin "8") (pinfunction "P_8") (pintype "bidirectional"))
      (node (ref "LED2") (pin "C") (pinfunction "C_C") (pintype "passive"))
      (node (ref "U3") (pin "102") (pinfunction "LED2-1_102") (pintype "bidirectional"))
    )
    (net (code "10") (name "L1-2") (class "Default")
      (node (ref "J4") (pin "9") (pinfunction "P_9") (pintype "bidirectional"))
      (node (ref "J5") (pin "9") (pinfunction "P_9") (pintype "bidirectional"))
      (node (ref "LED4") (pin "C") (pinfunction "C_C") (pintype "passive"))
      (node (ref "U3") (pin "101") (pinfunction "LED2-2_101") (pintype "bidirectional"))
    )
    (net (code "11") (name "L2-1") (class "Default")
      (node (ref "J4") (pin "18") (pinfunction "P_18") (pintype "bidirectional"))
      (node (ref "J5") (pin "18") (pinfunction "P_18") (pintype "bidirectional"))
      (node (ref "LED3") (pin "C") (pinfunction "C_C") (pintype "passive"))
      (node (ref "U3") (pin "97") (pinfunction "LED3-1_97") (pintype "bidirectional"))
    )
    (net (code "12") (name "L2-2") (class "Default")
      (node (ref "J4") (pin "19") (pinfunction "P_19") (pintype "bidirectional"))
      (node (ref "J5") (pin "19") (pinfunction "P_19") (pintype "bidirectional"))
      (node (ref "LED5") (pin "C") (pinfunction "C_C") (pintype "passive"))
      (node (ref "U3") (pin "96") (pinfunction "LED3-2_96") (pintype "bidirectional"))
    )
    (net (code "13") (name "L3-1") (class "Default")
      (node (ref "J6") (pin "L2") (pinfunction "L2_L2") (pintype "passive"))
      (node (ref "U3") (pin "105") (pinfunction "LED1-1_105") (pintype "bidirectional"))
    )
    (net (code "14") (name "L3-2") (class "Default")
      (node (ref "J6") (pin "L4") (pinfunction "L4_L4") (pintype "passive"))
      (node (ref "U3") (pin "104") (pinfunction "LED1-2_104") (pintype "bidirectional"))
    )
    (net (code "15") (name "Net-(C5-Pad1)") (class "Default")
      (node (ref "C5") (pin "1") (pinfunction "1_1") (pintype "passive"))
      (node (ref "R11") (pin "1") (pinfunction "1_1") (pintype "passive"))
      (node (ref "R14") (pin "1") (pinfunction "1_1") (pintype "passive"))
      (node (ref "R5") (pin "1") (pinfunction "1_1") (pintype "passive"))
    )
    (net (code "16") (name "Net-(C6-Pad1)") (class "Default")
      (node (ref "C6") (pin "1") (pinfunction "1_1") (pintype "passive"))
      (node (ref "R13") (pin "1") (pinfunction "1_1") (pintype "passive"))
      (node (ref "R15") (pin "1") (pinfunction "1_1") (pintype "passive"))
      (node (ref "R7") (pin "1") (pinfunction "1_1") (pintype "passive"))
    )
    (net (code "17") (name "Net-(C15-Pad1)") (class "Default")
      (node (ref "C15") (pin "1") (pinfunction "1_1") (pintype "passive"))
      (node (ref "R20") (pin "1") (pinfunction "1_1") (pintype "passive"))
      (node (ref "R22") (pin "1") (pinfunction "1_1") (pintype "passive"))
    )
    (net (code "18") (name "Net-(C16-Pad1)") (class "Default")
      (node (ref "C16") (pin "1") (pinfunction "1_1") (pintype "passive"))
      (node (ref "R21") (pin "1") (pinfunction "1_1") (pintype "passive"))
      (node (ref "R23") (pin "1") (pinfunction "1_1") (pintype "passive"))
    )
    (net (code "19") (name "Net-(C17-Pad1)") (class "Default")
      (node (ref "C17") (pin "1") (pinfunction "1_1") (pintype "passive"))
      (node (ref "R24") (pin "1") (pinfunction "1_1") (pintype "passive"))
      (node (ref "R26") (pin "1") (pinfunction "1_1") (pintype "passive"))
    )
    (net (code "20") (name "Net-(C18-Pad1)") (class "Default")
      (node (ref "C18") (pin "1") (pinfunction "1_1") (pintype "passive"))
      (node (ref "R25") (pin "1") (pinfunction "1_1") (pintype "passive"))
      (node (ref "R27") (pin "1") (pinfunction "1_1") (pintype "passive"))
    )
    (net (code "21") (name "Net-(C20-Pad1)") (class "Default")
      (node (ref "C20") (pin "1") (pinfunction "1_1") (pintype "passive"))
      (node (ref "R30") (pin "1") (pinfunction "1_1") (pintype "passive"))
      (node (ref "R31") (pin "1") (pinfunction "1_1") (pintype "passive"))
    )
    (net (code "22") (name "Net-(C21-Pad1)") (class "Default")
      (node (ref "C21") (pin "1") (pinfunction "1_1") (pintype "passive"))
      (node (ref "R32") (pin "1") (pinfunction "1_1") (pintype "passive"))
      (node (ref "R33") (pin "1") (pinfunction "1_1") (pintype "passive"))
    )
    (net (code "23") (name "Net-(D1-C)") (class "Default")
      (node (ref "C3") (pin "1") (pinfunction "1_1") (pintype "passive"))
      (node (ref "C4") (pin "1") (pinfunction "1_1") (pintype "passive"))
      (node (ref "D1") (pin "1") (pinfunction "C_1") (pintype "passive"))
      (node (ref "F1") (pin "2") (pinfunction "2_2") (pintype "passive"))
      (node (ref "L1") (pin "1") (pinfunction "1_1") (pintype "passive"))
    )
    (net (code "24") (name "Net-(J1B-S)") (class "Default")
      (node (ref "F1") (pin "1") (pinfunction "1_1") (pintype "passive"))
      (node (ref "J1") (pin "2") (pinfunction "S_2") (pintype "passive"))
    )
    (net (code "25") (name "Net-(J2-Pad4)") (class "Default")
      (node (ref "J2") (pin "4") (pinfunction "4_4") (pintype "passive"))
      (node (ref "R1") (pin "2") (pinfunction "2_2") (pintype "passive"))
    )
    (net (code "26") (name "Net-(J2-Pad5)") (class "Default")
      (node (ref "J2") (pin "5") (pinfunction "5_5") (pintype "passive"))
      (node (ref "R12") (pin "2") (pinfunction "2_2") (pintype "passive"))
    )
    (net (code "27") (name "Net-(J2-Pad7)") (class "Default")
      (node (ref "J2") (pin "7") (pinfunction "7_7") (pintype "passive"))
      (node (ref "R9") (pin "2") (pinfunction "2_2") (pintype "passive"))
    )
    (net (code "28") (name "Net-(J2-Pad8)") (class "Default")
      (node (ref "J2") (pin "8") (pinfunction "8_8") (pintype "passive"))
      (node (ref "R6") (pin "2") (pinfunction "2_2") (pintype "passive"))
    )
    (net (code "29") (name "Net-(J3-Pad4)") (class "Default")
      (node (ref "J3") (pin "4") (pinfunction "4_4") (pintype "passive"))
      (node (ref "R2") (pin "2") (pinfunction "2_2") (pintype "passive"))
    )
    (net (code "30") (name "Net-(J3-Pad5)") (class "Default")
      (node (ref "J3") (pin "5") (pinfunction "5_5") (pintype "passive"))
      (node (ref "R10") (pin "2") (pinfunction "2_2") (pintype "passive"))
    )
    (net (code "31") (name "Net-(J3-Pad7)") (class "Default")
      (node (ref "J3") (pin "7") (pinfunction "7_7") (pintype "passive"))
      (node (ref "R8") (pin "2") (pinfunction "2_2") (pintype "passive"))
    )
    (net (code "32") (name "Net-(J3-Pad8)") (class "Default")
      (node (ref "J3") (pin "8") (pinfunction "8_8") (pintype "passive"))
      (node (ref "R4") (pin "2") (pinfunction "2_2") (pintype "passive"))
    )
    (net (code "33") (name "Net-(J6-PadL1)") (class "Default")
      (node (ref "J6") (pin "L1") (pinfunction "L1_L1") (pintype "passive"))
      (node (ref "R28") (pin "2") (pinfunction "2_2") (pintype "passive"))
    )
    (net (code "34") (name "Net-(J6-PadL3)") (class "Default")
      (node (ref "J6") (pin "L3") (pinfunction "L3_L3") (pintype "passive"))
      (node (ref "R29") (pin "2") (pinfunction "2_2") (pintype "passive"))
    )
    (net (code "35") (name "Net-(LED1-PadA)") (class "Default")
      (node (ref "LED1") (pin "A") (pinfunction "A_A") (pintype "passive"))
      (node (ref "R3") (pin "1") (pinfunction "1_1") (pintype "passive"))
    )
    (net (code "36") (name "Net-(LED2-PadA)") (class "Default")
      (node (ref "LED2") (pin "A") (pinfunction "A_A") (pintype "passive"))
      (node (ref "R16") (pin "1") (pinfunction "1_1") (pintype "passive"))
    )
    (net (code "37") (name "Net-(LED3-PadA)") (class "Default")
      (node (ref "LED3") (pin "A") (pinfunction "A_A") (pintype "passive"))
      (node (ref "R17") (pin "1") (pinfunction "1_1") (pintype "passive"))
    )
    (net (code "38") (name "Net-(LED4-PadA)") (class "Default")
      (node (ref "LED4") (pin "A") (pinfunction "A_A") (pintype "passive"))
      (node (ref "R18") (pin "1") (pinfunction "1_1") (pintype "passive"))
    )
    (net (code "39") (name "Net-(LED5-PadA)") (class "Default")
      (node (ref "LED5") (pin "A") (pinfunction "A_A") (pintype "passive"))
      (node (ref "R19") (pin "1") (pinfunction "1_1") (pintype "passive"))
    )
    (net (code "40") (name "Net-(R1-Pad1)") (class "Default")
      (node (ref "R1") (pin "1") (pinfunction "1_1") (pintype "passive"))
      (node (ref "R6") (pin "1") (pinfunction "1_1") (pintype "passive"))
      (node (ref "R7") (pin "2") (pinfunction "2_2") (pintype "passive"))
    )
    (net (code "41") (name "Net-(R2-Pad1)") (class "Default")
      (node (ref "R2") (pin "1") (pinfunction "1_1") (pintype "passive"))
      (node (ref "R4") (pin "1") (pinfunction "1_1") (pintype "passive"))
      (node (ref "R5") (pin "2") (pinfunction "2_2") (pintype "passive"))
    )
    (net (code "42") (name "Net-(R10-Pad1)") (class "Default")
      (node (ref "R10") (pin "1") (pinfunction "1_1") (pintype "passive"))
      (node (ref "R11") (pin "2") (pinfunction "2_2") (pintype "passive"))
      (node (ref "R8") (pin "1") (pinfunction "1_1") (pintype "passive"))
    )
    (net (code "43") (name "Net-(R12-Pad1)") (class "Default")
      (node (ref "R12") (pin "1") (pinfunction "1_1") (pintype "passive"))
      (node (ref "R13") (pin "2") (pinfunction "2_2") (pintype "passive"))
      (node (ref "R9") (pin "1") (pinfunction "1_1") (pintype "passive"))
    )
    (net (code "44") (name "PS0") (class "Default")
      (node (ref "R37") (pin "1") (pinfunction "1_1") (pintype "passive"))
      (node (ref "U3") (pin "114") (pinfunction "PS0_114") (pintype "input"))
    )
    (net (code "45") (name "PS1") (class "Default")
      (node (ref "R36") (pin "1") (pinfunction "1_1") (pintype "passive"))
      (node (ref "U3") (pin "113") (pinfunction "PS1_113") (pintype "input"))
    )
    (net (code "46") (name "PWRDN_N") (class "Default")
      (node (ref "U3") (pin "47") (pinfunction "PWRDN_N_47") (pintype "input"))
    )
    (net (code "47") (name "RST_N") (class "Default")
      (node (ref "C23") (pin "1") (pinfunction "1_1") (pintype "passive"))
      (node (ref "D2") (pin "A") (pinfunction "2_A") (pintype "passive"))
      (node (ref "R34") (pin "1") (pinfunction "1_1") (pintype "passive"))
      (node (ref "U3") (pin "115") (pinfunction "RST_N_115") (pintype "input"))
    )
    (net (code "48") (name "RX1_ISO_N") (class "Default")
      (node (ref "R24") (pin "2") (pinfunction "2_2") (pintype "passive"))
      (node (ref "T1") (pin "8") (pinfunction "RD-_8") (pintype "bidirectional"))
      (node (ref "U3") (pin "11") (pinfunction "RXM2_11") (pintype "input"))
    )
    (net (code "49") (name "RX1_ISO_P") (class "Default")
      (node (ref "R26") (pin "2") (pinfunction "2_2") (pintype "passive"))
      (node (ref "T1") (pin "6") (pinfunction "RD+_6") (pintype "bidirectional"))
      (node (ref "U3") (pin "10") (pinfunction "RXP2_10") (pintype "input"))
    )
    (net (code "50") (name "RX1_N") (class "Default")
      (node (ref "J2") (pin "2") (pinfunction "2_2") (pintype "passive"))
      (node (ref "J4") (pin "3") (pinfunction "P_3") (pintype "bidirectional"))
      (node (ref "J5") (pin "3") (pinfunction "P_3") (pintype "bidirectional"))
      (node (ref "T1") (pin "9") (pinfunction "RX-_9") (pintype "bidirectional"))
    )
    (net (code "51") (name "RX1_P") (class "Default")
      (node (ref "J2") (pin "1") (pinfunction "1_1") (pintype "passive"))
      (node (ref "J4") (pin "2") (pinfunction "P_2") (pintype "bidirectional"))
      (node (ref "J5") (pin "2") (pinfunction "P_2") (pintype "bidirectional"))
      (node (ref "T1") (pin "11") (pinfunction "RX+_11") (pintype "bidirectional"))
    )
    (net (code "52") (name "RX2_ISO_N") (class "Default")
      (node (ref "R25") (pin "2") (pinfunction "2_2") (pintype "passive"))
      (node (ref "T2") (pin "8") (pinfunction "RD-_8") (pintype "bidirectional"))
      (node (ref "U3") (pin "20") (pinfunction "RXM3_20") (pintype "input"))
    )
    (net (code "53") (name "RX2_ISO_P") (class "Default")
      (node (ref "R27") (pin "2") (pinfunction "2_2") (pintype "passive"))
      (node (ref "T2") (pin "6") (pinfunction "RD+_6") (pintype "bidirectional"))
      (node (ref "U3") (pin "19") (pinfunction "RXP3_19") (pintype "input"))
    )
    (net (code "54") (name "RX2_N") (class "Default")
      (node (ref "J3") (pin "2") (pinfunction "2_2") (pintype "passive"))
      (node (ref "J4") (pin "13") (pinfunction "P_13") (pintype "bidirectional"))
      (node (ref "J5") (pin "13") (pinfunction "P_13") (pintype "bidirectional"))
      (node (ref "T2") (pin "9") (pinfunction "RX-_9") (pintype "bidirectional"))
    )
    (net (code "55") (name "RX2_P") (class "Default")
      (node (ref "J3") (pin "1") (pinfunction "1_1") (pintype "passive"))
      (node (ref "J4") (pin "12") (pinfunction "P_12") (pintype "bidirectional"))
      (node (ref "J5") (pin "12") (pinfunction "P_12") (pintype "bidirectional"))
      (node (ref "T2") (pin "11") (pinfunction "RX+_11") (pintype "bidirectional"))
    )
    (net (code "56") (name "RX3_ISO_N") (class "Default")
      (node (ref "J6") (pin "R8") (pinfunction "RD-_R8") (pintype "input"))
      (node (ref "R33") (pin "2") (pinfunction "2_2") (pintype "passive"))
      (node (ref "U3") (pin "5") (pinfunction "RXM1_5") (pintype "input"))
    )
    (net (code "57") (name "RX3_ISO_P") (class "Default")
      (node (ref "J6") (pin "R7") (pinfunction "RD+_R7") (pintype "input"))
      (node (ref "R32") (pin "2") (pinfunction "2_2") (pintype "passive"))
      (node (ref "U3") (pin "4") (pinfunction "RXP1_4") (pintype "input"))
    )
    (net (code "58") (name "SCL") (class "Default")
      (node (ref "R40") (pin "1") (pinfunction "1_1") (pintype "passive"))
      (node (ref "R41") (pin "1") (pinfunction "1_1") (pintype "passive"))
      (node (ref "U3") (pin "110") (pinfunction "SPIC/SCL_110") (pintype "bidirectional"))
    )
    (net (code "59") (name "SCL_CPU") (class "Default")
      (node (ref "R41") (pin "2") (pinfunction "2_2") (pintype "passive"))
      (node (ref "TP2") (pin "TP") (pinfunction "TP_TP") (pintype "input"))
    )
    (net (code "60") (name "SCL_EEPROM") (class "Default")
      (node (ref "R40") (pin "2") (pinfunction "2_2") (pintype "passive"))
      (node (ref "U4") (pin "6") (pinfunction "SCL_6") (pintype "input"))
    )
    (net (code "61") (name "SDA") (class "Default")
      (node (ref "R38") (pin "1") (pinfunction "1_1") (pintype "passive"))
      (node (ref "R39") (pin "1") (pinfunction "1_1") (pintype "passive"))
      (node (ref "U3") (pin "111") (pinfunction "SSPID/SDA_111") (pintype "bidirectional"))
    )
    (net (code "62") (name "SDA_CPU") (class "Default")
      (node (ref "R39") (pin "2") (pinfunction "2_2") (pintype "passive"))
      (node (ref "TP3") (pin "TP") (pinfunction "TP_TP") (pintype "input"))
    )
    (net (code "63") (name "SDA_EEPROM") (class "Default")
      (node (ref "R38") (pin "2") (pinfunction "2_2") (pintype "passive"))
      (node (ref "U4") (pin "5") (pinfunction "SDA_5") (pintype "bidirectional"))
    )
    (net (code "64") (name "SPIQ") (class "Default")
      (node (ref "R42") (pin "1") (pinfunction "1_1") (pintype "passive"))
      (node (ref "U3") (pin "109") (pinfunction "SPIQ_109") (pintype "output"))
    )
    (net (code "65") (name "SPIQ_CPU") (class "Default")
      (node (ref "R42") (pin "2") (pinfunction "2_2") (pintype "passive"))
      (node (ref "TP1") (pin "TP") (pinfunction "TP_TP") (pintype "input"))
    )
    (net (code "66") (name "SPIS-N") (class "Default")
      (node (ref "R43") (pin "1") (pinfunction "1_1") (pintype "passive"))
      (node (ref "U3") (pin "112") (pinfunction "SPIS_N_112") (pintype "input"))
    )
    (net (code "67") (name "SPIS-N_CPU") (class "Default")
      (node (ref "R43") (pin "2") (pinfunction "2_2") (pintype "passive"))
      (node (ref "TP4") (pin "TP") (pinfunction "TP_TP") (pintype "input"))
    )
    (net (code "68") (name "TX1_ISO_N") (class "Default")
      (node (ref "R20") (pin "2") (pinfunction "2_2") (pintype "passive"))
      (node (ref "T1") (pin "3") (pinfunction "TD-_3") (pintype "bidirectional"))
      (node (ref "U3") (pin "14") (pinfunction "TXM2_14") (pintype "output"))
    )
    (net (code "69") (name "TX1_ISO_P") (class "Default")
      (node (ref "R22") (pin "2") (pinfunction "2_2") (pintype "passive"))
      (node (ref "T1") (pin "1") (pinfunction "TD+_1") (pintype "bidirectional"))
      (node (ref "U3") (pin "13") (pinfunction "TXP2_13") (pintype "output"))
    )
    (net (code "70") (name "TX1_N") (class "Default")
      (node (ref "J2") (pin "6") (pinfunction "6_6") (pintype "passive"))
      (node (ref "J4") (pin "6") (pinfunction "P_6") (pintype "bidirectional"))
      (node (ref "J5") (pin "6") (pinfunction "P_6") (pintype "bidirectional"))
      (node (ref "T1") (pin "14") (pinfunction "TX-_14") (pintype "bidirectional"))
    )
    (net (code "71") (name "TX1_P") (class "Default")
      (node (ref "J2") (pin "3") (pinfunction "3_3") (pintype "passive"))
      (node (ref "J4") (pin "5") (pinfunction "P_5") (pintype "bidirectional"))
      (node (ref "J5") (pin "5") (pinfunction "P_5") (pintype "bidirectional"))
      (node (ref "T1") (pin "16") (pinfunction "TX+_16") (pintype "bidirectional"))
    )
    (net (code "72") (name "TX2_ISO_N") (class "Default")
      (node (ref "R21") (pin "2") (pinfunction "2_2") (pintype "passive"))
      (node (ref "T2") (pin "3") (pinfunction "TD-_3") (pintype "bidirectional"))
      (node (ref "U3") (pin "23") (pinfunction "TXM3_23") (pintype "output"))
    )
    (net (code "73") (name "TX2_ISO_P") (class "Default")
      (node (ref "R23") (pin "2") (pinfunction "2_2") (pintype "passive"))
      (node (ref "T2") (pin "1") (pinfunction "TD+_1") (pintype "bidirectional"))
      (node (ref "U3") (pin "22") (pinfunction "TXP3_22") (pintype "output"))
    )
    (net (code "74") (name "TX2_N") (class "Default")
      (node (ref "J3") (pin "6") (pinfunction "6_6") (pintype "passive"))
      (node (ref "J4") (pin "16") (pinfunction "P_16") (pintype "bidirectional"))
      (node (ref "J5") (pin "16") (pinfunction "P_16") (pintype "bidirectional"))
      (node (ref "T2") (pin "14") (pinfunction "TX-_14") (pintype "bidirectional"))
    )
    (net (code "75") (name "TX2_P") (class "Default")
      (node (ref "J3") (pin "3") (pinfunction "3_3") (pintype "passive"))
      (node (ref "J4") (pin "15") (pinfunction "P_15") (pintype "bidirectional"))
      (node (ref "J5") (pin "15") (pinfunction "P_15") (pintype "bidirectional"))
      (node (ref "T2") (pin "16") (pinfunction "TX+_16") (pintype "bidirectional"))
    )
    (net (code "76") (name "TX3_ISO_N") (class "Default")
      (node (ref "J6") (pin "R2") (pinfunction "TD-_R2") (pintype "input"))
      (node (ref "R31") (pin "2") (pinfunction "2_2") (pintype "passive"))
      (node (ref "U3") (pin "8") (pinfunction "TXM1_8") (pintype "output"))
    )
    (net (code "77") (name "TX3_ISO_P") (class "Default")
      (node (ref "J6") (pin "R1") (pinfunction "TD+_R1") (pintype "input"))
      (node (ref "R30") (pin "2") (pinfunction "2_2") (pintype "passive"))
      (node (ref "U3") (pin "7") (pinfunction "TXP1_7") (pintype "output"))
    )
    (net (code "78") (name "X1") (class "Default")
      (node (ref "C22") (pin "1") (pinfunction "1_1") (pintype "passive"))
      (node (ref "U3") (pin "121") (pinfunction "X1_121") (pintype "input"))
      (node (ref "X1") (pin "1") (pinfunction "1_1") (pintype "passive"))
    )
    (net (code "79") (name "X2") (class "Default")
      (node (ref "C24") (pin "1") (pinfunction "1_1") (pintype "passive"))
      (node (ref "U3") (pin "122") (pinfunction "X2_122") (pintype "output"))
      (node (ref "X1") (pin "3") (pinfunction "3_3") (pintype "passive"))
    )
    (net (code "80") (name "unconnected-(J4F-P-Pad14)") (class "Default")
      (node (ref "J4") (pin "14") (pinfunction "P_14") (pintype "bidirectional"))
    )
    (net (code "81") (name "unconnected-(J4I-P-Pad17)") (class "Default")
      (node (ref "J4") (pin "17") (pinfunction "P_17") (pintype "bidirectional"))
    )
    (net (code "82") (name "unconnected-(J4O-P-Pad4)") (class "Default")
      (node (ref "J4") (pin "4") (pinfunction "P_4") (pintype "bidirectional"))
    )
    (net (code "83") (name "unconnected-(J4R-P-Pad7)") (class "Default")
      (node (ref "J4") (pin "7") (pinfunction "P_7") (pintype "bidirectional"))
    )
    (net (code "84") (name "unconnected-(J5F-P-Pad14)") (class "Default")
      (node (ref "J5") (pin "14") (pinfunction "P_14") (pintype "bidirectional"))
    )
    (net (code "85") (name "unconnected-(J5I-P-Pad17)") (class "Default")
      (node (ref "J5") (pin "17") (pinfunction "P_17") (pintype "bidirectional"))
    )
    (net (code "86") (name "unconnected-(J5O-P-Pad4)") (class "Default")
      (node (ref "J5") (pin "4") (pinfunction "P_4") (pintype "bidirectional"))
    )
    (net (code "87") (name "unconnected-(J5R-P-Pad7)") (class "Default")
      (node (ref "J5") (pin "7") (pinfunction "P_7") (pintype "bidirectional"))
    )
    (net (code "88") (name "unconnected-(U3A-FXSD4-Pad39)") (class "Default")
      (node (ref "U3") (pin "39") (pinfunction "FXSD4_39") (pintype "input"))
    )
    (net (code "89") (name "unconnected-(U3A-FXSD5{slash}FXSD3-Pad38)") (class "Default")
      (node (ref "U3") (pin "38") (pinfunction "FXSD5/FXSD3_38") (pintype "input"))
    )
    (net (code "90") (name "unconnected-(U3A-MDI-XDIS-Pad1)") (class "Default")
      (node (ref "U3") (pin "1") (pinfunction "MDI-XDIS_1") (pintype "input"))
    )
    (net (code "91") (name "unconnected-(U3A-MUX1-Pad45)") (class "Default")
      (node (ref "U3") (pin "45") (pinfunction "MUX1_45") (pintype "passive"))
    )
    (net (code "92") (name "unconnected-(U3A-MUX2-Pad46)") (class "Default")
      (node (ref "U3") (pin "46") (pinfunction "MUX2_46") (pintype "passive"))
    )
    (net (code "93") (name "unconnected-(U3A-PMRXC-Pad60)") (class "Default")
      (node (ref "U3") (pin "60") (pinfunction "PMRXC_60") (pintype "output"))
    )
    (net (code "94") (name "unconnected-(U3A-PMRXD1-Pad64)") (class "Default")
      (node (ref "U3") (pin "64") (pinfunction "PMRXD1_64") (pintype "bidirectional"))
    )
    (net (code "95") (name "unconnected-(U3A-PMRXD2-Pad63)") (class "Default")
      (node (ref "U3") (pin "63") (pinfunction "PMRXD2_63") (pintype "bidirectional"))
    )
    (net (code "96") (name "unconnected-(U3A-PMRXD3-Pad62)") (class "Default")
      (node (ref "U3") (pin "62") (pinfunction "PMRXD3_62") (pintype "bidirectional"))
    )
    (net (code "97") (name "unconnected-(U3A-PMRXDV-Pad61)") (class "Default")
      (node (ref "U3") (pin "61") (pinfunction "PMRXDV_61") (pintype "bidirectional"))
    )
    (net (code "98") (name "unconnected-(U3A-PMTXC-Pad57)") (class "Default")
      (node (ref "U3") (pin "57") (pinfunction "PMTXC_57") (pintype "output"))
    )
    (net (code "99") (name "unconnected-(U3A-PMTXD0-Pad55)") (class "Default")
      (node (ref "U3") (pin "55") (pinfunction "PMTXD0_55") (pintype "input"))
    )
    (net (code "100") (name "unconnected-(U3A-PMTXD1-Pad54)") (class "Default")
      (node (ref "U3") (pin "54") (pinfunction "PMTXD1_54") (pintype "input"))
    )
    (net (code "101") (name "unconnected-(U3A-PMTXD2-Pad53)") (class "Default")
      (node (ref "U3") (pin "53") (pinfunction "PMTXD2_53") (pintype "input"))
    )
    (net (code "102") (name "unconnected-(U3A-PMTXD3-Pad52)") (class "Default")
      (node (ref "U3") (pin "52") (pinfunction "PMTXD3_52") (pintype "input"))
    )
    (net (code "103") (name "unconnected-(U3A-PMTXEN-Pad51)") (class "Default")
      (node (ref "U3") (pin "51") (pinfunction "PMTXEN_51") (pintype "input"))
    )
    (net (code "104") (name "unconnected-(U3A-PMTXER-Pad56)") (class "Default")
      (node (ref "U3") (pin "56") (pinfunction "PMTXER_56") (pintype "input"))
    )
    (net (code "105") (name "unconnected-(U3A-RESERVE-Pad48)") (class "Default")
      (node (ref "U3") (pin "48") (pinfunction "RESERVE_48") (pintype "passive"))
    )
    (net (code "106") (name "unconnected-(U3B-LED1-0-Pad106)") (class "Default")
      (node (ref "U3") (pin "106") (pinfunction "LED1-0_106") (pintype "bidirectional"))
    )
    (net (code "107") (name "unconnected-(U3B-LED2-0-Pad103)") (class "Default")
      (node (ref "U3") (pin "103") (pinfunction "LED2-0_103") (pintype "bidirectional"))
    )
    (net (code "108") (name "unconnected-(U3B-LED3-0-Pad98)") (class "Default")
      (node (ref "U3") (pin "98") (pinfunction "LED3-0_98") (pintype "bidirectional"))
    )
    (net (code "109") (name "unconnected-(U3B-LED4-0-Pad95)") (class "Default")
      (node (ref "U3") (pin "95") (pinfunction "LED4-0_95") (pintype "bidirectional"))
    )
    (net (code "110") (name "unconnected-(U3B-LED4-1-Pad94)") (class "Default")
      (node (ref "U3") (pin "94") (pinfunction "LED4-1_94") (pintype "bidirectional"))
    )
    (net (code "111") (name "unconnected-(U3B-LED4-2-Pad93)") (class "Default")
      (node (ref "U3") (pin "93") (pinfunction "LED4-2_93") (pintype "bidirectional"))
    )
    (net (code "112") (name "unconnected-(U3B-LED5-0-Pad92)") (class "Default")
      (node (ref "U3") (pin "92") (pinfunction "LED5-0_92") (pintype "bidirectional"))
    )
    (net (code "113") (name "unconnected-(U3B-LED5-1-Pad91)") (class "Default")
      (node (ref "U3") (pin "91") (pinfunction "LED5-1_91") (pintype "bidirectional"))
    )
    (net (code "114") (name "unconnected-(U3B-LED5-2-Pad90)") (class "Default")
      (node (ref "U3") (pin "90") (pinfunction "LED5-2_90") (pintype "bidirectional"))
    )
    (net (code "115") (name "unconnected-(U3B-MDC-Pad107)") (class "Default")
      (node (ref "U3") (pin "107") (pinfunction "MDC_107") (pintype "input"))
    )
    (net (code "116") (name "unconnected-(U3B-MDIO-Pad108)") (class "Default")
      (node (ref "U3") (pin "108") (pinfunction "MDIO_108") (pintype "bidirectional"))
    )
    (net (code "117") (name "unconnected-(U3B-NC-Pad120)") (class "Default")
      (node (ref "U3") (pin "120") (pinfunction "NC_120") (pintype "no_connect"))
    )
    (net (code "118") (name "unconnected-(U3B-PCOL-Pad68)") (class "Default")
      (node (ref "U3") (pin "68") (pinfunction "PCOL_68") (pintype "bidirectional"))
    )
    (net (code "119") (name "unconnected-(U3B-PCRS-Pad67)") (class "Default")
      (node (ref "U3") (pin "67") (pinfunction "PCRS_67") (pintype "bidirectional"))
    )
    (net (code "120") (name "unconnected-(U3B-PMRXD0-Pad65)") (class "Default")
      (node (ref "U3") (pin "65") (pinfunction "PMRXD0_65") (pintype "bidirectional"))
    )
    (net (code "121") (name "unconnected-(U3B-PMRXER-Pad66)") (class "Default")
      (node (ref "U3") (pin "66") (pinfunction "PMRXER_66") (pintype "bidirectional"))
    )
    (net (code "122") (name "unconnected-(U3B-SCANEN-Pad119)") (class "Default")
      (node (ref "U3") (pin "119") (pinfunction "SCANEN_119") (pintype "input"))
    )
    (net (code "123") (name "unconnected-(U3B-SCOL-Pad84)") (class "Default")
      (node (ref "U3") (pin "84") (pinfunction "SCOL_84") (pintype "bidirectional"))
    )
    (net (code "124") (name "unconnected-(U3B-SCONF0-Pad87)") (class "Default")
      (node (ref "U3") (pin "87") (pinfunction "SCONF0_87") (pintype "input"))
    )
    (net (code "125") (name "unconnected-(U3B-SCONF1-Pad86)") (class "Default")
      (node (ref "U3") (pin "86") (pinfunction "SCONF1_86") (pintype "input"))
    )
    (net (code "126") (name "unconnected-(U3B-SCRS-Pad85)") (class "Default")
      (node (ref "U3") (pin "85") (pinfunction "SCRS_85") (pintype "bidirectional"))
    )
    (net (code "127") (name "unconnected-(U3B-SMRXC-Pad78)") (class "Default")
      (node (ref "U3") (pin "78") (pinfunction "SMRXC_78") (pintype "bidirectional"))
    )
    (net (code "128") (name "unconnected-(U3B-SMRXD0-Pad83)") (class "Default")
      (node (ref "U3") (pin "83") (pinfunction "SMRXD0_83") (pintype "bidirectional"))
    )
    (net (code "129") (name "unconnected-(U3B-SMRXD1-Pad82)") (class "Default")
      (node (ref "U3") (pin "82") (pinfunction "SMRXD1_82") (pintype "bidirectional"))
    )
    (net (code "130") (name "unconnected-(U3B-SMRXD2-Pad81)") (class "Default")
      (node (ref "U3") (pin "81") (pinfunction "SMRXD2_81") (pintype "bidirectional"))
    )
    (net (code "131") (name "unconnected-(U3B-SMRXD3-Pad80)") (class "Default")
      (node (ref "U3") (pin "80") (pinfunction "SMRXD3_80") (pintype "bidirectional"))
    )
    (net (code "132") (name "unconnected-(U3B-SMRXDV-Pad79)") (class "Default")
      (node (ref "U3") (pin "79") (pinfunction "SMRXDV_79") (pintype "bidirectional"))
    )
    (net (code "133") (name "unconnected-(U3B-SMTXC-Pad75)") (class "Default")
      (node (ref "U3") (pin "75") (pinfunction "SMTXC_75") (pintype "bidirectional"))
    )
    (net (code "134") (name "unconnected-(U3B-SMTXD0-Pad73)") (class "Default")
      (node (ref "U3") (pin "73") (pinfunction "SMTXD0_73") (pintype "input"))
    )
    (net (code "135") (name "unconnected-(U3B-SMTXD1-Pad72)") (class "Default")
      (node (ref "U3") (pin "72") (pinfunction "SMTXD1_72") (pintype "input"))
    )
    (net (code "136") (name "unconnected-(U3B-SMTXD2-Pad71)") (class "Default")
      (node (ref "U3") (pin "71") (pinfunction "SMTXD2_71") (pintype "input"))
    )
    (net (code "137") (name "unconnected-(U3B-SMTXD3-Pad70)") (class "Default")
      (node (ref "U3") (pin "70") (pinfunction "SMTXD3_70") (pintype "input"))
    )
    (net (code "138") (name "unconnected-(U3B-SMTXEN-Pad69)") (class "Default")
      (node (ref "U3") (pin "69") (pinfunction "SMTXEN_69") (pintype "input"))
    )
    (net (code "139") (name "unconnected-(U3B-SMTXER-Pad74)") (class "Default")
      (node (ref "U3") (pin "74") (pinfunction "SMTXER_74") (pintype "input"))
    )
    (net (code "140") (name "unconnected-(U3B-TEST2-Pad128)") (class "Default")
      (node (ref "U3") (pin "128") (pinfunction "TEST2_128") (pintype "passive"))
    )
    (net (code "141") (name "unconnected-(U3B-TESTEN-Pad118)") (class "Default")
      (node (ref "U3") (pin "118") (pinfunction "TESTEN_118") (pintype "input"))
    )
  )
)
